# Charger.net
KiCad netlist of a schematic drawn in Altium Designer
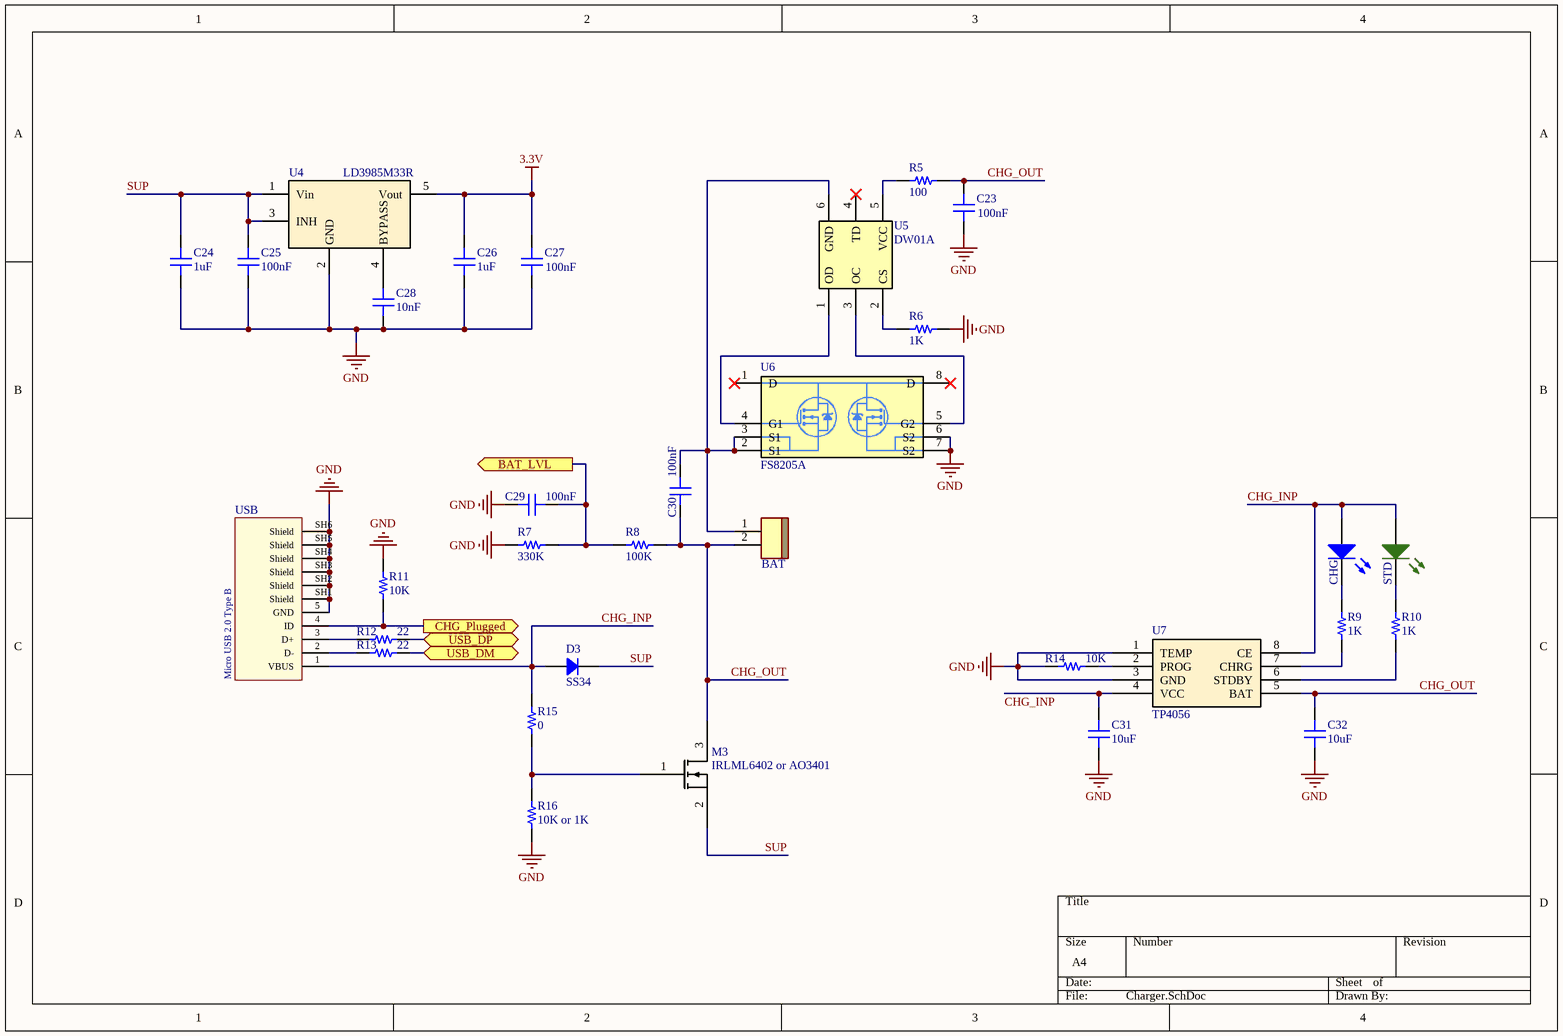
[diagram p0: Charger.SchDoc]

(export (version "E")
  (design (tool "Eeschema 10.0.6"))
  (components
    (comp (ref "BAT")
      (value "JST BxB-PH-K 2Pin")
      (footprint "JST B2B-PH-K")
      (description "Connector Header Through Hole 0.079\" (2.00mm)")
      (fields (field (name "PARTNUMBER") "B2B-PH-K-S(LF)(SN)"))
      (libsource (lib "Conn Terminal") (part "JST BxB-PH-K 2Pin"))
    )
    (comp (ref "C23")
      (value "100nF")
      (footprint "CAP 0603_1608")
      (description "SMT Capacitor")
      (libsource (lib "Capacitor") (part "Cap 0603"))
    )
    (comp (ref "C24")
      (value "1uF")
      (footprint "CAP 0603_1608")
      (description "SMT Capacitor")
      (libsource (lib "Capacitor") (part "Cap 0603"))
    )
    (comp (ref "C25")
      (value "100nF")
      (footprint "CAP 0603_1608")
      (description "SMT Capacitor")
      (libsource (lib "Capacitor") (part "Cap 0603"))
    )
    (comp (ref "C26")
      (value "1uF")
      (footprint "CAP 0603_1608")
      (description "SMT Capacitor")
      (libsource (lib "Capacitor") (part "Cap 0603"))
    )
    (comp (ref "C27")
      (value "100nF")
      (footprint "CAP 0603_1608")
      (description "SMT Capacitor")
      (libsource (lib "Capacitor") (part "Cap 0603"))
    )
    (comp (ref "C28")
      (value "10nF")
      (footprint "CAP 0603_1608")
      (description "SMT Capacitor")
      (libsource (lib "Capacitor") (part "Cap 0603"))
    )
    (comp (ref "C29")
      (value "100nF")
      (footprint "CAP 0603_1608")
      (description "SMT Capacitor")
      (libsource (lib "Capacitor") (part "Cap 0603"))
    )
    (comp (ref "C30")
      (value "100nF")
      (footprint "CAP 0603_1608")
      (description "SMT Capacitor")
      (libsource (lib "Capacitor") (part "Cap 0603"))
    )
    (comp (ref "C31")
      (value "10uF")
      (footprint "CAP 0603_1608")
      (description "SMT Capacitor")
      (libsource (lib "Capacitor") (part "Cap 0603"))
    )
    (comp (ref "C32")
      (value "10uF")
      (footprint "CAP 0603_1608")
      (description "SMT Capacitor")
      (libsource (lib "Capacitor") (part "Cap 0603"))
    )
    (comp (ref "CHG")
      (value "LED SMD 0603 BLUE")
      (footprint "LED_0603_RED")
      (libsource (lib "Led") (part "LED SMD 0603 BLUE"))
    )
    (comp (ref "D3")
      (value "SS34")
      (footprint "DO-214AC SMA")
      (description "Diode Standard 1000V 1A Surface Mount SMA")
      (libsource (lib "Diode") (part "US1M (SMD SMA)"))
    )
    (comp (ref "M3")
      (value "IRLML6402 or AO3401")
      (footprint "SOT-23")
      (libsource (lib "Salman_lib") (part "2N7002A"))
    )
    (comp (ref "R5")
      (value "100")
      (footprint "RES 0603_1608")
      (description "SMT Resistor")
      (libsource (lib "Resistor") (part "Res 0603"))
    )
    (comp (ref "R6")
      (value "1K")
      (footprint "RES 0603_1608")
      (description "SMT Resistor")
      (libsource (lib "Resistor") (part "Res 0603"))
    )
    (comp (ref "R7")
      (value "330K")
      (footprint "RES 0402_1005")
      (description "SMT Resistor")
      (libsource (lib "Resistor") (part "Res 0402"))
    )
    (comp (ref "R8")
      (value "100K")
      (footprint "RES 0402_1005")
      (description "SMT Resistor")
      (libsource (lib "Resistor") (part "Res 0402"))
    )
    (comp (ref "R9")
      (value "1K")
      (footprint "RES 0603_1608")
      (description "SMT Resistor")
      (libsource (lib "Resistor") (part "Res 0603"))
    )
    (comp (ref "R10")
      (value "1K")
      (footprint "RES 0603_1608")
      (description "SMT Resistor")
      (libsource (lib "Resistor") (part "Res 0603"))
    )
    (comp (ref "R11")
      (value "10K")
      (footprint "RES 0603_1608")
      (description "SMT Resistor")
      (libsource (lib "Resistor") (part "Res 0603"))
    )
    (comp (ref "R12")
      (value "22")
      (footprint "RES 0402_1005")
      (description "SMT Resistor")
      (libsource (lib "Resistor") (part "Res 0402"))
    )
    (comp (ref "R13")
      (value "22")
      (footprint "RES 0402_1005")
      (description "SMT Resistor")
      (libsource (lib "Resistor") (part "Res 0402"))
    )
    (comp (ref "R14")
      (value "10K")
      (footprint "RES 0603_1608")
      (description "SMT Resistor")
      (libsource (lib "Resistor") (part "Res 0603"))
    )
    (comp (ref "R15")
      (value "0")
      (footprint "RES 0603_1608")
      (description "SMT Resistor")
      (libsource (lib "Resistor") (part "Res 0603"))
    )
    (comp (ref "R16")
      (value "10K or 1K")
      (footprint "RES 0603_1608")
      (description "SMT Resistor")
      (libsource (lib "Resistor") (part "Res 0603"))
    )
    (comp (ref "STD")
      (value "LED SMD 0603 GREEN")
      (footprint "LED_0603_GREEN")
      (libsource (lib "Led") (part "LED SMD 0603 GREEN"))
    )
    (comp (ref "U4")
      (value "LD3985M33R")
      (footprint "SOT23-5L")
      (description "3.3V LDO Regulatoe")
      (libsource (lib "Salman_lib") (part "LD3985M33R"))
    )
    (comp (ref "U5") (value "DW01A") (footprint "SOT-23-6pin") (libsource (lib "Salman_lib") (part "DW01A")))
    (comp (ref "U6") (value "FS8205A") (footprint "TTSOP-8") (libsource (lib "Salman_lib") (part "FS8205A")))
    (comp (ref "U7") (value "TP4056") (footprint "SOIC-8") (libsource (lib "Salman_lib") (part "TP4056")))
    (comp (ref "USB")
      (value "Micro USB 2.0 Type B")
      (footprint "USB_MICRO_B_BM_SHT")
      (description "USB - micro B  Receptacle Connector 5 Position Surface Mount, Right Angle")
      (fields (field (name "PARTNUMBER") "UB-MC5BR3-SD204-4S-1-TB NMP"))
      (libsource (lib "Conn Usb") (part "Micro USB 2.0 Type B Horizonta (SMD) UB-MC5BR3-SD204-4S-1-TB NMP"))
    )
  )
  (nets
    (net (code "1") (name "/BAT_LVL") (class "Default")
      (node (ref "C29") (pin "1") (pinfunction "1_1") (pintype "passive"))
      (node (ref "R7") (pin "2") (pinfunction "2_2") (pintype "passive"))
      (node (ref "R8") (pin "1") (pinfunction "1_1") (pintype "passive"))
    )
    (net (code "2") (name "/CHG_INP") (class "Default")
      (node (ref "C31") (pin "1") (pinfunction "1_1") (pintype "passive"))
      (node (ref "CHG") (pin "1") (pinfunction "A_1") (pintype "passive"))
      (node (ref "D3") (pin "1") (pinfunction "1_1") (pintype "passive"))
      (node (ref "R15") (pin "2") (pinfunction "2_2") (pintype "passive"))
      (node (ref "STD") (pin "1") (pinfunction "A_1") (pintype "passive"))
      (node (ref "U7") (pin "4") (pinfunction "VCC_4") (pintype "passive"))
      (node (ref "U7") (pin "8") (pinfunction "CE_8") (pintype "passive"))
      (node (ref "USB") (pin "1") (pinfunction "VBUS_1") (pintype "passive"))
    )
    (net (code "3") (name "/CHG_OUT") (class "Default")
      (node (ref "BAT") (pin "2") (pinfunction "2_2") (pintype "passive"))
      (node (ref "C23") (pin "2") (pinfunction "2_2") (pintype "passive"))
      (node (ref "C30") (pin "2") (pinfunction "2_2") (pintype "passive"))
      (node (ref "C32") (pin "1") (pinfunction "1_1") (pintype "passive"))
      (node (ref "M3") (pin "3") (pintype "passive"))
      (node (ref "R5") (pin "2") (pinfunction "2_2") (pintype "passive"))
      (node (ref "R8") (pin "2") (pinfunction "2_2") (pintype "passive"))
      (node (ref "U7") (pin "5") (pinfunction "BAT_5") (pintype "passive"))
    )
    (net (code "4") (name "/CHG_Plugged") (class "Default")
      (node (ref "R11") (pin "1") (pinfunction "1_1") (pintype "passive"))
      (node (ref "USB") (pin "4") (pinfunction "ID_4") (pintype "passive"))
    )
    (net (code "5") (name "/SUP") (class "Default")
      (node (ref "C24") (pin "2") (pinfunction "2_2") (pintype "passive"))
      (node (ref "C25") (pin "2") (pinfunction "2_2") (pintype "passive"))
      (node (ref "D3") (pin "2") (pinfunction "2_2") (pintype "passive"))
      (node (ref "M3") (pin "2") (pintype "passive"))
      (node (ref "U4") (pin "1") (pinfunction "Vin_1") (pintype "passive"))
      (node (ref "U4") (pin "3") (pinfunction "INH_3") (pintype "passive"))
    )
    (net (code "6") (name "/USB_DM") (class "Default")
      (node (ref "R13") (pin "2") (pinfunction "2_2") (pintype "passive"))
    )
    (net (code "7") (name "/USB_DP") (class "Default")
      (node (ref "R12") (pin "2") (pinfunction "2_2") (pintype "passive"))
    )
    (net (code "8") (name "3.3V") (class "Default")
      (node (ref "C26") (pin "2") (pinfunction "2_2") (pintype "passive"))
      (node (ref "C27") (pin "2") (pinfunction "2_2") (pintype "passive"))
      (node (ref "U4") (pin "5") (pinfunction "Vout_5") (pintype "passive"))
    )
    (net (code "9") (name "GND") (class "Default")
      (node (ref "C23") (pin "1") (pinfunction "1_1") (pintype "passive"))
      (node (ref "C24") (pin "1") (pinfunction "1_1") (pintype "passive"))
      (node (ref "C25") (pin "1") (pinfunction "1_1") (pintype "passive"))
      (node (ref "C26") (pin "1") (pinfunction "1_1") (pintype "passive"))
      (node (ref "C27") (pin "1") (pinfunction "1_1") (pintype "passive"))
      (node (ref "C28") (pin "1") (pinfunction "1_1") (pintype "passive"))
      (node (ref "C29") (pin "2") (pinfunction "2_2") (pintype "passive"))
      (node (ref "C31") (pin "2") (pinfunction "2_2") (pintype "passive"))
      (node (ref "C32") (pin "2") (pinfunction "2_2") (pintype "passive"))
      (node (ref "R11") (pin "2") (pinfunction "2_2") (pintype "passive"))
      (node (ref "R14") (pin "1") (pinfunction "1_1") (pintype "passive"))
      (node (ref "R16") (pin "1") (pinfunction "1_1") (pintype "passive"))
      (node (ref "R6") (pin "1") (pinfunction "1_1") (pintype "passive"))
      (node (ref "R7") (pin "1") (pinfunction "1_1") (pintype "passive"))
      (node (ref "U4") (pin "2") (pinfunction "GND_2") (pintype "passive"))
      (node (ref "U6") (pin "6") (pinfunction "S2_6") (pintype "passive"))
      (node (ref "U6") (pin "7") (pinfunction "S2_7") (pintype "passive"))
      (node (ref "U7") (pin "1") (pinfunction "TEMP_1") (pintype "passive"))
      (node (ref "U7") (pin "3") (pinfunction "GND_3") (pintype "passive"))
      (node (ref "USB") (pin "5") (pinfunction "GND_5") (pintype "passive"))
      (node (ref "USB") (pin "SH1") (pinfunction "Shield_SH1") (pintype "passive"))
      (node (ref "USB") (pin "SH2") (pinfunction "Shield_SH2") (pintype "passive"))
      (node (ref "USB") (pin "SH3") (pinfunction "Shield_SH3") (pintype "passive"))
      (node (ref "USB") (pin "SH4") (pinfunction "Shield_SH4") (pintype "passive"))
      (node (ref "USB") (pin "SH5") (pinfunction "Shield_SH5") (pintype "passive"))
      (node (ref "USB") (pin "SH6") (pinfunction "Shield_SH6") (pintype "passive"))
    )
    (net (code "10") (name "Net-(CHG-K)") (class "Default")
      (node (ref "CHG") (pin "2") (pinfunction "K_2") (pintype "passive"))
      (node (ref "R9") (pin "2") (pinfunction "2_2") (pintype "passive"))
    )
    (net (code "11") (name "Net-(M3-Pad1)") (class "Default")
      (node (ref "M3") (pin "1") (pintype "passive"))
      (node (ref "R15") (pin "1") (pinfunction "1_1") (pintype "passive"))
      (node (ref "R16") (pin "2") (pinfunction "2_2") (pintype "passive"))
    )
    (net (code "12") (name "Net-(STD-K)") (class "Default")
      (node (ref "R10") (pin "2") (pinfunction "2_2") (pintype "passive"))
      (node (ref "STD") (pin "2") (pinfunction "K_2") (pintype "passive"))
    )
    (net (code "13") (name "Net-(U4-BYPASS)") (class "Default")
      (node (ref "C28") (pin "2") (pinfunction "2_2") (pintype "passive"))
      (node (ref "U4") (pin "4") (pinfunction "BYPASS_4") (pintype "passive"))
    )
    (net (code "14") (name "Net-(U5-CS)") (class "Default")
      (node (ref "R6") (pin "2") (pinfunction "2_2") (pintype "passive"))
      (node (ref "U5") (pin "2") (pinfunction "CS_2") (pintype "passive"))
    )
    (net (code "15") (name "Net-(U5-GND)") (class "Default")
      (node (ref "BAT") (pin "1") (pinfunction "1_1") (pintype "passive"))
      (node (ref "C30") (pin "1") (pinfunction "1_1") (pintype "passive"))
      (node (ref "U5") (pin "6") (pinfunction "GND_6") (pintype "passive"))
      (node (ref "U6") (pin "2") (pinfunction "S1_2") (pintype "passive"))
      (node (ref "U6") (pin "3") (pinfunction "S1_3") (pintype "passive"))
    )
    (net (code "16") (name "Net-(U5-OC)") (class "Default")
      (node (ref "U5") (pin "3") (pinfunction "OC_3") (pintype "passive"))
      (node (ref "U6") (pin "5") (pinfunction "G2_5") (pintype "passive"))
    )
    (net (code "17") (name "Net-(U5-OD)") (class "Default")
      (node (ref "U5") (pin "1") (pinfunction "OD_1") (pintype "passive"))
      (node (ref "U6") (pin "4") (pinfunction "G1_4") (pintype "passive"))
    )
    (net (code "18") (name "Net-(U5-VCC)") (class "Default")
      (node (ref "R5") (pin "1") (pinfunction "1_1") (pintype "passive"))
      (node (ref "U5") (pin "5") (pinfunction "VCC_5") (pintype "passive"))
    )
    (net (code "19") (name "Net-(U7-CHRG)") (class "Default")
      (node (ref "R9") (pin "1") (pinfunction "1_1") (pintype "passive"))
      (node (ref "U7") (pin "7") (pinfunction "CHRG_7") (pintype "passive"))
    )
    (net (code "20") (name "Net-(U7-PROG)") (class "Default")
      (node (ref "R14") (pin "2") (pinfunction "2_2") (pintype "passive"))
      (node (ref "U7") (pin "2") (pinfunction "PROG_2") (pintype "passive"))
    )
    (net (code "21") (name "Net-(U7-STDBY)") (class "Default")
      (node (ref "R10") (pin "1") (pinfunction "1_1") (pintype "passive"))
      (node (ref "U7") (pin "6") (pinfunction "STDBY_6") (pintype "passive"))
    )
    (net (code "22") (name "Net-(USB-D+)") (class "Default")
      (node (ref "R12") (pin "1") (pinfunction "1_1") (pintype "passive"))
      (node (ref "USB") (pin "3") (pinfunction "D+_3") (pintype "passive"))
    )
    (net (code "23") (name "Net-(USB-D-)") (class "Default")
      (node (ref "R13") (pin "1") (pinfunction "1_1") (pintype "passive"))
      (node (ref "USB") (pin "2") (pinfunction "D-_2") (pintype "passive"))
    )
    (net (code "24") (name "unconnected-(U5-TD-Pad4)") (class "Default")
      (node (ref "U5") (pin "4") (pinfunction "TD_4") (pintype "passive+no_connect"))
    )
    (net (code "25") (name "unconnected-(U6-D-Pad1)") (class "Default")
      (node (ref "U6") (pin "1") (pinfunction "D_1") (pintype "passive+no_connect"))
    )
    (net (code "26") (name "unconnected-(U6-D-Pad8)") (class "Default")
      (node (ref "U6") (pin "8") (pinfunction "D_8") (pintype "passive+no_connect"))
    )
  )
)
